# LocalizationBoard_B_1_0_Schematic_CG.net
KiCad netlist of a schematic drawn in Altium Designer
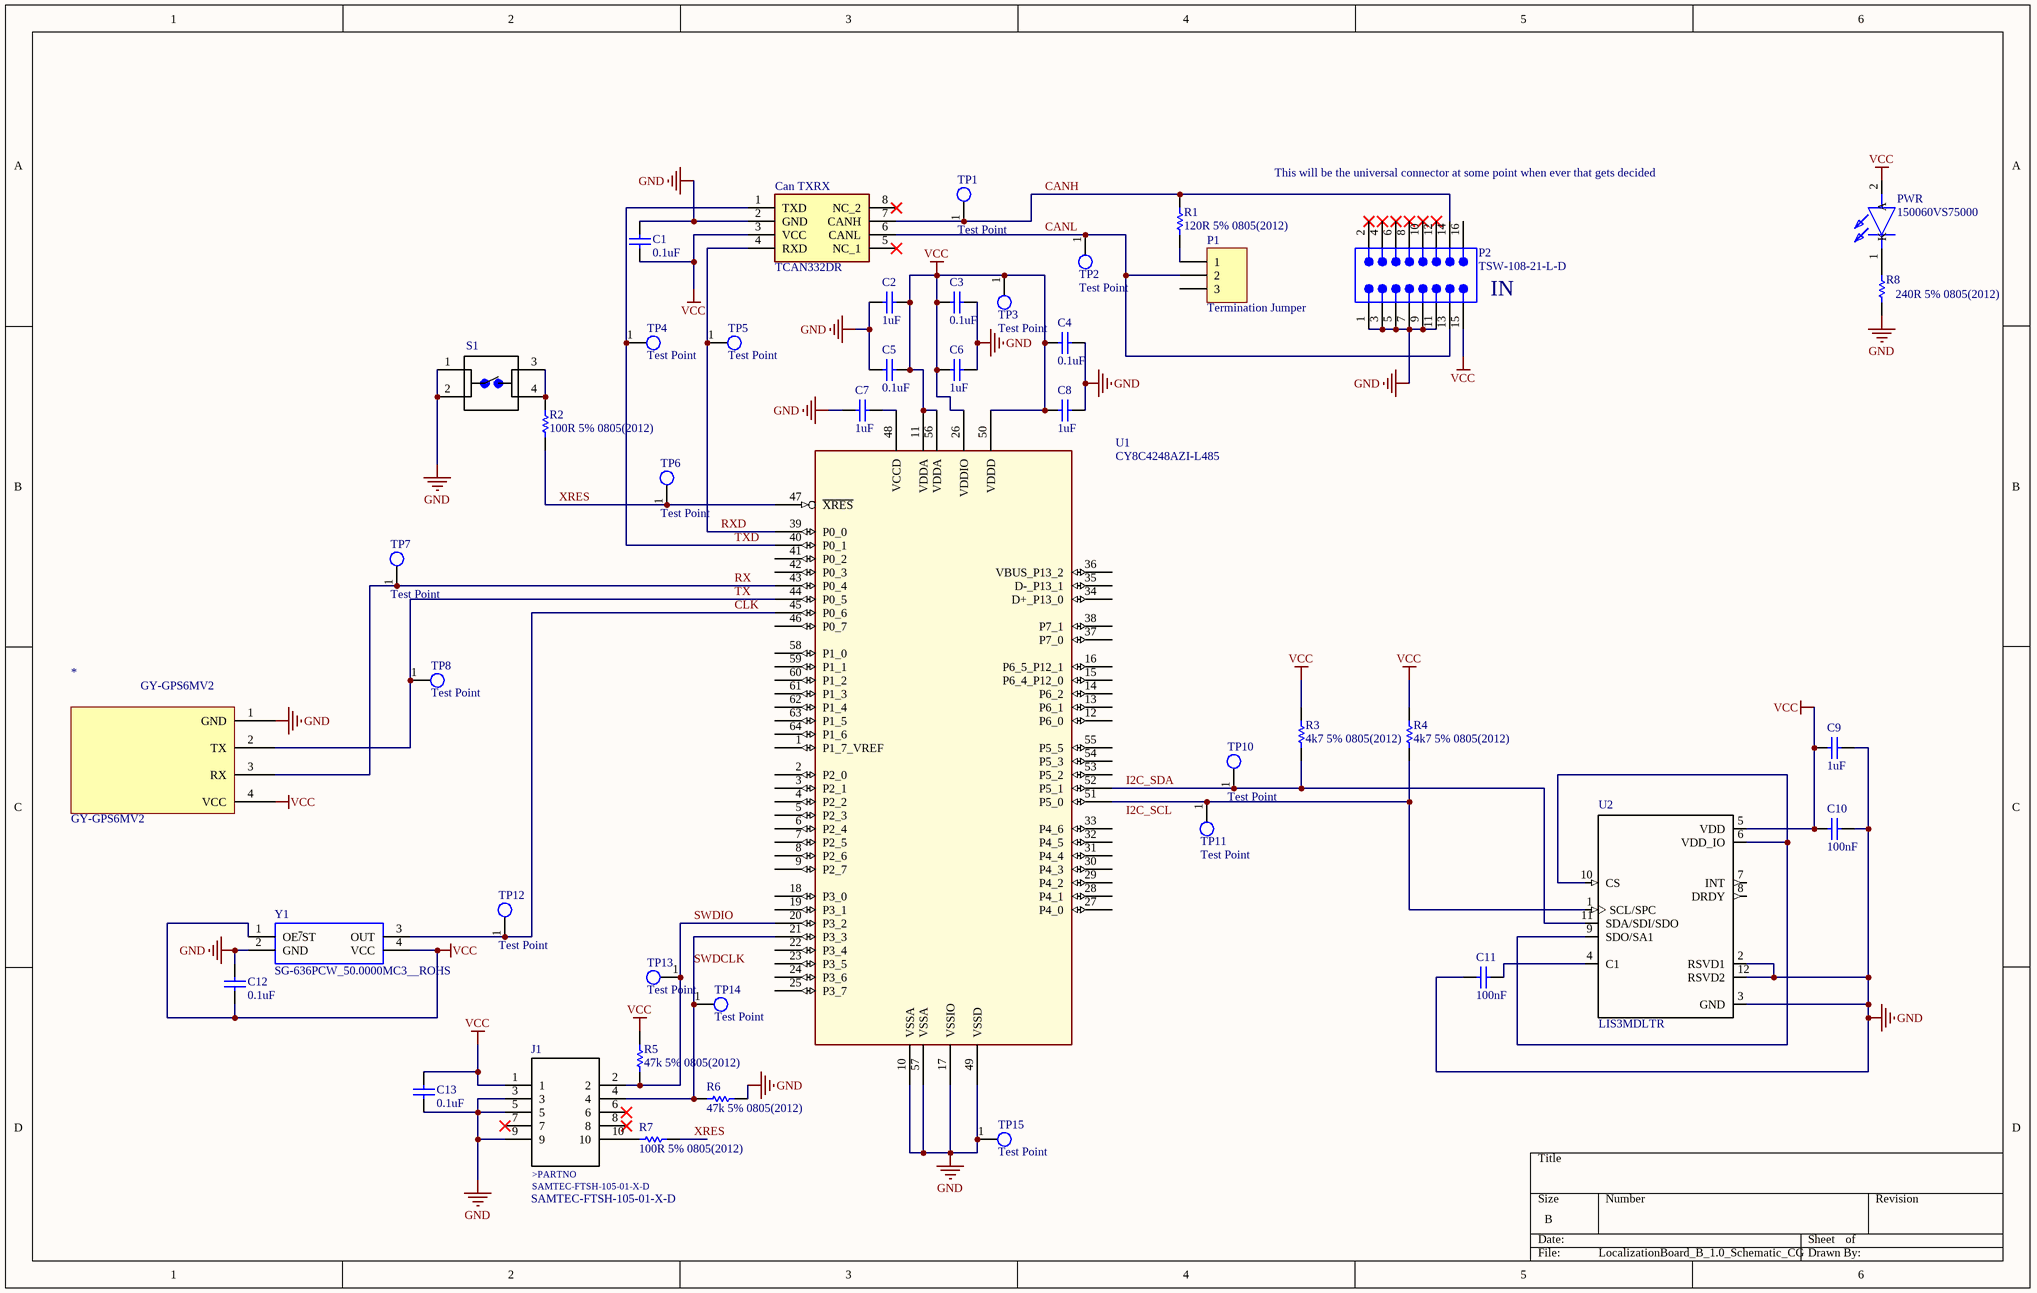
[diagram p0: LocalizationBoard_B_1.0_Schematic_CG.SchDoc]

(export (version "E")
  (design (tool "Eeschema 10.0.6"))
  (components
    (comp (ref "*")
      (value "GY-GPS6MV2")
      (footprint "PCBComponent_1 - duplicate2")
      (libsource (lib "Husky Robotics Standard Library 2019-2020") (part "GY-GPS6MV2"))
    )
    (comp (ref "C1")
      (value "0.1uF")
      (footprint "CAPC0805(2012)100_M")
      (description "CAP 33pF 200V ±1% 0805 (2012 Metric) Thickness 1mm SMD")
      (fields (field (name "TOLERANCE") "Â±1%"))
      (libsource (lib "Altium Content Vault") (part "CAP"))
    )
    (comp (ref "C2")
      (value "1uF")
      (footprint "CAPC0805(2012)100_M")
      (description "CAP 33pF 200V ±1% 0805 (2012 Metric) Thickness 1mm SMD")
      (fields (field (name "TOLERANCE") "Â±1%"))
      (libsource (lib "Altium Content Vault") (part "CAP"))
    )
    (comp (ref "C3")
      (value "0.1uF")
      (footprint "CAPC0805(2012)100_M")
      (description "CAP 33pF 200V ±1% 0805 (2012 Metric) Thickness 1mm SMD")
      (fields (field (name "TOLERANCE") "Â±1%"))
      (libsource (lib "Altium Content Vault") (part "CAP"))
    )
    (comp (ref "C4")
      (value "0.1uF")
      (footprint "CAPC0805(2012)100_N")
      (description "CAP 33pF 200V ±1% 0805 (2012 Metric) Thickness 1mm SMD")
      (fields (field (name "TOLERANCE") "Â±1%"))
      (libsource (lib "Altium Content Vault") (part "CAP"))
    )
    (comp (ref "C5")
      (value "0.1uF")
      (footprint "CAPC0805(2012)100_M")
      (description "CAP 33pF 200V ±1% 0805 (2012 Metric) Thickness 1mm SMD")
      (fields (field (name "TOLERANCE") "Â±1%"))
      (libsource (lib "Altium Content Vault") (part "CAP"))
    )
    (comp (ref "C6")
      (value "1uF")
      (footprint "CAPC0805(2012)100_M")
      (description "CAP 33pF 200V ±1% 0805 (2012 Metric) Thickness 1mm SMD")
      (fields (field (name "TOLERANCE") "Â±1%"))
      (libsource (lib "Altium Content Vault") (part "CAP"))
    )
    (comp (ref "C7")
      (value "1uF")
      (footprint "CAPC0805(2012)100_M")
      (description "CAP 33pF 200V ±1% 0805 (2012 Metric) Thickness 1mm SMD")
      (fields (field (name "TOLERANCE") "Â±1%"))
      (libsource (lib "Altium Content Vault") (part "CAP"))
    )
    (comp (ref "C8")
      (value "1uF")
      (footprint "CAPC0805(2012)100_M")
      (description "CAP 33pF 200V ±1% 0805 (2012 Metric) Thickness 1mm SMD")
      (fields (field (name "TOLERANCE") "Â±1%"))
      (libsource (lib "Altium Content Vault") (part "CAP"))
    )
    (comp (ref "C9")
      (value "1uF")
      (footprint "CAPC0805(2012)100_M")
      (description "CAP 33pF 200V ±1% 0805 (2012 Metric) Thickness 1mm SMD")
      (fields (field (name "TOLERANCE") "Â±1%"))
      (libsource (lib "Altium Content Vault") (part "CAP"))
    )
    (comp (ref "C10")
      (value "100nF")
      (footprint "CAPC0805(2012)100_M")
      (description "CAP 33pF 200V ±1% 0805 (2012 Metric) Thickness 1mm SMD")
      (fields (field (name "TOLERANCE") "Â±1%"))
      (libsource (lib "Altium Content Vault") (part "CAP"))
    )
    (comp (ref "C11")
      (value "100nF")
      (footprint "CAPC0805(2012)100_M")
      (description "CAP 33pF 200V ±1% 0805 (2012 Metric) Thickness 1mm SMD")
      (fields (field (name "TOLERANCE") "Â±1%"))
      (libsource (lib "Altium Content Vault") (part "CAP"))
    )
    (comp (ref "C12")
      (value "0.1uF")
      (footprint "CAPC0805(2012)100_M")
      (description "CAP 33pF 200V ±1% 0805 (2012 Metric) Thickness 1mm SMD")
      (fields (field (name "TOLERANCE") "Â±1%"))
      (libsource (lib "Altium Content Vault") (part "CAP"))
    )
    (comp (ref "C13")
      (value "0.1uF")
      (footprint "CAPC0805(2012)100_M")
      (description "CAP 33pF 200V ±1% 0805 (2012 Metric) Thickness 1mm SMD")
      (fields (field (name "TOLERANCE") "Â±1%"))
      (libsource (lib "Altium Content Vault") (part "CAP"))
    )
    (comp (ref "Can TXRX")
      (value "TCAN332DR")
      (footprint "SamacSys:SOIC127P600X175-8N")
      (description "Integrated Circuit")
      (fields (field (name "MOUSER PART NUMBER") "595-TCAN332DR"))
      (libsource (lib "*") (part "TCAN332DR"))
    )
    (comp (ref "J1")
      (value "SAMTEC-FTSH-105-01-X-D")
      (footprint "SAMTEC-FTSH-105-01-X-D")
      (libsource (lib "Husky Robotics Standard Library 2019-2020") (part "SAMTEC-FTSH-105-01-X-D"))
    )
    (comp (ref "P1")
      (value "Termination Jumper")
      (footprint "HDR1X3")
      (description "Header, 3-Pin")
      (fields (field (name "PUBLISHER") "Altium Limited"))
      (libsource (lib "Miscellaneous Connectors") (part "Header 3"))
    )
    (comp (ref "P2")
      (value "TSW-108-21-L-D")
      (footprint "SMTC-TSW-108-21-X-D")
      (fields (field (name "MANUFACTURER") "Samtec"))
      (libsource (lib "Altium Content Vault") (part "SMTC-TSW-108-X-X-D"))
    )
    (comp (ref "PWR")
      (value "150060VS75000")
      (footprint "SamacSys:LEDC1608X80N")
      (description "LED")
      (fields
        (field (name "MOUSER PART NUMBER") "710-150060VS75000")
        (field (name "RS PART NUMBER") "8154215P")
      )
      (libsource (lib "*") (part "150060VS75000"))
    )
    (comp (ref "R1")
      (value "120R 5% 0805(2012)")
      (footprint "RESC0805(2012)_N")
      (description "120R 0.125W 5% 0805 (2012 Metric)  SMD")
      (fields (field (name "TOLERANCE") "5 %") (field (name "POWER") "0.125 W"))
      (libsource (lib "Husky Robotics Standard Library 2019-2020") (part "120R 5% 0805"))
    )
    (comp (ref "R2")
      (value "100R 5% 0805(2012)")
      (footprint "RESC0805(2012)_N")
      (description "120R 0.125W 5% 0805 (2012 Metric)  SMD")
      (fields (field (name "TOLERANCE") "5 %") (field (name "POWER") "0.125 W"))
      (libsource (lib "Husky Robotics Standard Library 2019-2020") (part "120R 5% 0805"))
    )
    (comp (ref "R3")
      (value "4k7 5% 0805(2012)")
      (footprint "RESC0805(2012)_N")
      (description "120R 0.125W 5% 0805 (2012 Metric)  SMD")
      (fields (field (name "TOLERANCE") "5 %") (field (name "POWER") "0.125 W"))
      (libsource (lib "Husky Robotics Standard Library 2019-2020") (part "120R 5% 0805"))
    )
    (comp (ref "R4")
      (value "4k7 5% 0805(2012)")
      (footprint "RESC0805(2012)_N")
      (description "120R 0.125W 5% 0805 (2012 Metric)  SMD")
      (fields (field (name "TOLERANCE") "5 %") (field (name "POWER") "0.125 W"))
      (libsource (lib "Husky Robotics Standard Library 2019-2020") (part "120R 5% 0805"))
    )
    (comp (ref "R5")
      (value "47k 5% 0805(2012)")
      (footprint "RESC0805(2012)_N")
      (description "120R 0.125W 5% 0805 (2012 Metric)  SMD")
      (fields (field (name "TOLERANCE") "5 %") (field (name "POWER") "0.125 W"))
      (libsource (lib "Husky Robotics Standard Library 2019-2020") (part "120R 5% 0805"))
    )
    (comp (ref "R6")
      (value "47k 5% 0805(2012)")
      (footprint "RESC0805(2012)_N")
      (description "120R 0.125W 5% 0805 (2012 Metric)  SMD")
      (fields (field (name "TOLERANCE") "5 %") (field (name "POWER") "0.125 W"))
      (libsource (lib "Husky Robotics Standard Library 2019-2020") (part "120R 5% 0805"))
    )
    (comp (ref "R7")
      (value "100R 5% 0805(2012)")
      (footprint "RESC0805(2012)_N")
      (description "120R 0.125W 5% 0805 (2012 Metric)  SMD")
      (fields (field (name "TOLERANCE") "5 %") (field (name "POWER") "0.125 W"))
      (libsource (lib "Husky Robotics Standard Library 2019-2020") (part "120R 5% 0805"))
    )
    (comp (ref "R8")
      (value "240R 5% 0805(2012)")
      (footprint "RESC0805(2012)_N")
      (description "120R 0.125W 5% 0805 (2012 Metric)  SMD")
      (fields (field (name "TOLERANCE") "5 %") (field (name "POWER") "0.125 W"))
      (libsource (lib "Husky Robotics Standard Library 2019-2020") (part "120R 5% 0805"))
    )
    (comp (ref "S1")
      (value "1825910-7")
      (footprint "Switch 6mm 24V (NO)")
      (description "FSM4JAH=6MM TACT SWITCH, HIGH TEMP")
      (fields (field (name "MF") "TE Connectivity") (field (name "DIGI-KEY_PART_NUMBER") "450-1804-ND"))
      (libsource (lib "Husky Robotics Standard Library 2019-2020") (part "Switch 6mm 24V (NO)"))
    )
    (comp (ref "TP1")
      (value "Test Point")
      (footprint "Test Point Through-hole")
      (libsource (lib "Husky Robotics Standard Library 2019-2020") (part "Test Point"))
    )
    (comp (ref "TP2")
      (value "Test Point")
      (footprint "Test Point Through-hole")
      (libsource (lib "Husky Robotics Standard Library 2019-2020") (part "Test Point"))
    )
    (comp (ref "TP3")
      (value "Test Point")
      (footprint "Test Point Through-hole")
      (libsource (lib "Husky Robotics Standard Library 2019-2020") (part "Test Point"))
    )
    (comp (ref "TP4")
      (value "Test Point")
      (footprint "Test Point Through-hole")
      (libsource (lib "Husky Robotics Standard Library 2019-2020") (part "Test Point"))
    )
    (comp (ref "TP5")
      (value "Test Point")
      (footprint "Test Point Through-hole")
      (libsource (lib "Husky Robotics Standard Library 2019-2020") (part "Test Point"))
    )
    (comp (ref "TP6")
      (value "Test Point")
      (footprint "Test Point Through-hole")
      (libsource (lib "Husky Robotics Standard Library 2019-2020") (part "Test Point"))
    )
    (comp (ref "TP7")
      (value "Test Point")
      (footprint "Test Point Through-hole")
      (libsource (lib "Husky Robotics Standard Library 2019-2020") (part "Test Point"))
    )
    (comp (ref "TP8")
      (value "Test Point")
      (footprint "Test Point Through-hole")
      (libsource (lib "Husky Robotics Standard Library 2019-2020") (part "Test Point"))
    )
    (comp (ref "TP10")
      (value "Test Point")
      (footprint "Test Point Through-hole")
      (libsource (lib "Husky Robotics Standard Library 2019-2020") (part "Test Point"))
    )
    (comp (ref "TP11")
      (value "Test Point")
      (footprint "Test Point Through-hole")
      (libsource (lib "Husky Robotics Standard Library 2019-2020") (part "Test Point"))
    )
    (comp (ref "TP12")
      (value "Test Point")
      (footprint "Test Point Through-hole")
      (libsource (lib "Husky Robotics Standard Library 2019-2020") (part "Test Point"))
    )
    (comp (ref "TP13")
      (value "Test Point")
      (footprint "Test Point Through-hole")
      (libsource (lib "Husky Robotics Standard Library 2019-2020") (part "Test Point"))
    )
    (comp (ref "TP14")
      (value "Test Point")
      (footprint "Test Point Through-hole")
      (libsource (lib "Husky Robotics Standard Library 2019-2020") (part "Test Point"))
    )
    (comp (ref "TP15")
      (value "Test Point")
      (footprint "Test Point Through-hole")
      (libsource (lib "Husky Robotics Standard Library 2019-2020") (part "Test Point"))
    )
    (comp (ref "U1")
      (value "CY8C4248AZI-L485")
      (footprint "TQFP50P1200X1200X160-64N")
      (libsource (lib "Husky Robotics Standard Library 2019-2020") (part "CY8C4248AZI-L485"))
    )
    (comp (ref "U2")
      (value "LIS3MDLTR")
      (footprint "*XDCR_LIS3MDLTR")
      (description "LIS3MDL Series 3 Axis Â±2/Â±8/Â±12/Â±16 g 3.6V High Performance Magnetometer LGA-12")
      (fields (field (name "DIGI-KEY_PART_NUMBER") "497-13892-1-ND") (field (name "MF") "STMicroelectronics"))
      (libsource (lib "LIS3MDLTR") (part "LIS3MDLTR"))
    )
    (comp (ref "Y1")
      (value "SG-636PCW_50.0000MC3__ROHS")
      (footprint "SG-636")
      (description "Standard Clock Oscillators 50MHz 3.3Volt 100ppm -20C +70C")
      (fields (field (name "MANUFACTURER_PART_NUMBER") "SG-636PCW 50.0000MC3: ROHS"))
      (libsource (lib "Husky Robotics Standard Library 2019-2020") (part "SG-636"))
    )
  )
  (nets
    (net (code "1") (name "/CANH") (class "Default")
      (node (ref "Can TXRX") (pin "7") (pinfunction "CANH_7") (pintype "passive"))
      (node (ref "P2") (pin "14") (pinfunction "14_14") (pintype "passive"))
      (node (ref "R1") (pin "2") (pinfunction "2_2") (pintype "passive"))
      (node (ref "TP1") (pin "1") (pinfunction "1_1") (pintype "passive"))
    )
    (net (code "2") (name "/CANL") (class "Default")
      (node (ref "Can TXRX") (pin "6") (pinfunction "CANL_6") (pintype "passive"))
      (node (ref "P1") (pin "2") (pinfunction "2_2") (pintype "passive"))
      (node (ref "P2") (pin "13") (pinfunction "13_13") (pintype "passive"))
      (node (ref "TP2") (pin "1") (pinfunction "1_1") (pintype "passive"))
    )
    (net (code "3") (name "/CLK") (class "Default")
      (node (ref "TP12") (pin "1") (pinfunction "1_1") (pintype "passive"))
      (node (ref "U1") (pin "45") (pinfunction "P0_6_45") (pintype "bidirectional"))
      (node (ref "Y1") (pin "3") (pinfunction "OUT_3") (pintype "passive"))
    )
    (net (code "4") (name "/I2C_SCL") (class "Default")
      (node (ref "R4") (pin "1") (pinfunction "1_1") (pintype "passive"))
      (node (ref "TP11") (pin "1") (pinfunction "1_1") (pintype "passive"))
      (node (ref "U1") (pin "51") (pinfunction "P5_0_51") (pintype "bidirectional"))
      (node (ref "U2") (pin "1") (pinfunction "SCL/SPC_1") (pintype "input"))
    )
    (net (code "5") (name "/I2C_SDA") (class "Default")
      (node (ref "R3") (pin "1") (pinfunction "1_1") (pintype "passive"))
      (node (ref "TP10") (pin "1") (pinfunction "1_1") (pintype "passive"))
      (node (ref "U1") (pin "52") (pinfunction "P5_1_52") (pintype "bidirectional"))
      (node (ref "U2") (pin "11") (pinfunction "SDA/SDI/SDO_11") (pintype "bidirectional"))
    )
    (net (code "6") (name "/RX") (class "Default")
      (node (ref "*") (pin "3") (pinfunction "RX_3") (pintype "passive"))
      (node (ref "TP7") (pin "1") (pinfunction "1_1") (pintype "passive"))
      (node (ref "U1") (pin "43") (pinfunction "P0_4_43") (pintype "bidirectional"))
    )
    (net (code "7") (name "/RXD") (class "Default")
      (node (ref "Can TXRX") (pin "4") (pinfunction "RXD_4") (pintype "passive"))
      (node (ref "TP5") (pin "1") (pinfunction "1_1") (pintype "passive"))
      (node (ref "U1") (pin "39") (pinfunction "P0_0_39") (pintype "bidirectional"))
    )
    (net (code "8") (name "/SWDCLK") (class "Default")
      (node (ref "J1") (pin "4") (pinfunction "4_4") (pintype "passive"))
      (node (ref "R6") (pin "1") (pinfunction "1_1") (pintype "passive"))
      (node (ref "TP14") (pin "1") (pinfunction "1_1") (pintype "passive"))
      (node (ref "U1") (pin "21") (pinfunction "P3_3_21") (pintype "bidirectional"))
    )
    (net (code "9") (name "/SWDIO") (class "Default")
      (node (ref "J1") (pin "2") (pinfunction "2_2") (pintype "passive"))
      (node (ref "R5") (pin "1") (pinfunction "1_1") (pintype "passive"))
      (node (ref "TP13") (pin "1") (pinfunction "1_1") (pintype "passive"))
      (node (ref "U1") (pin "20") (pinfunction "P3_2_20") (pintype "bidirectional"))
    )
    (net (code "10") (name "/TX") (class "Default")
      (node (ref "*") (pin "2") (pinfunction "TX_2") (pintype "passive"))
      (node (ref "TP8") (pin "1") (pinfunction "1_1") (pintype "passive"))
      (node (ref "U1") (pin "44") (pinfunction "P0_5_44") (pintype "bidirectional"))
    )
    (net (code "11") (name "/TXD") (class "Default")
      (node (ref "Can TXRX") (pin "1") (pinfunction "TXD_1") (pintype "passive"))
      (node (ref "TP4") (pin "1") (pinfunction "1_1") (pintype "passive"))
      (node (ref "U1") (pin "40") (pinfunction "P0_1_40") (pintype "bidirectional"))
    )
    (net (code "12") (name "/XRES") (class "Default")
      (node (ref "R2") (pin "1") (pinfunction "1_1") (pintype "passive"))
      (node (ref "R7") (pin "1") (pinfunction "1_1") (pintype "passive"))
      (node (ref "TP6") (pin "1") (pinfunction "1_1") (pintype "passive"))
      (node (ref "U1") (pin "47") (pinfunction "~{XRES}_47") (pintype "input"))
    )
    (net (code "13") (name "GND") (class "Default")
      (node (ref "*") (pin "1") (pinfunction "GND_1") (pintype "passive"))
      (node (ref "C1") (pin "1") (pinfunction "1_1") (pintype "passive"))
      (node (ref "C10") (pin "1") (pinfunction "1_1") (pintype "passive"))
      (node (ref "C11") (pin "2") (pinfunction "2_2") (pintype "passive"))
      (node (ref "C12") (pin "1") (pinfunction "1_1") (pintype "passive"))
      (node (ref "C13") (pin "2") (pinfunction "2_2") (pintype "passive"))
      (node (ref "C2") (pin "2") (pinfunction "2_2") (pintype "passive"))
      (node (ref "C3") (pin "1") (pinfunction "1_1") (pintype "passive"))
      (node (ref "C4") (pin "1") (pinfunction "1_1") (pintype "passive"))
      (node (ref "C5") (pin "2") (pinfunction "2_2") (pintype "passive"))
      (node (ref "C6") (pin "1") (pinfunction "1_1") (pintype "passive"))
      (node (ref "C7") (pin "2") (pinfunction "2_2") (pintype "passive"))
      (node (ref "C8") (pin "1") (pinfunction "1_1") (pintype "passive"))
      (node (ref "C9") (pin "1") (pinfunction "1_1") (pintype "passive"))
      (node (ref "Can TXRX") (pin "2") (pinfunction "GND_2") (pintype "passive"))
      (node (ref "J1") (pin "3") (pinfunction "3_3") (pintype "passive"))
      (node (ref "J1") (pin "5") (pinfunction "5_5") (pintype "passive"))
      (node (ref "J1") (pin "9") (pinfunction "9_9") (pintype "passive"))
      (node (ref "P2") (pin "1") (pinfunction "1_1") (pintype "passive"))
      (node (ref "P2") (pin "11") (pinfunction "11_11") (pintype "passive"))
      (node (ref "P2") (pin "3") (pinfunction "3_3") (pintype "passive"))
      (node (ref "P2") (pin "5") (pinfunction "5_5") (pintype "passive"))
      (node (ref "P2") (pin "7") (pinfunction "7_7") (pintype "passive"))
      (node (ref "P2") (pin "9") (pinfunction "9_9") (pintype "passive"))
      (node (ref "R6") (pin "2") (pinfunction "2_2") (pintype "passive"))
      (node (ref "R8") (pin "1") (pinfunction "1_1") (pintype "passive"))
      (node (ref "S1") (pin "1") (pinfunction "1_1") (pintype "passive"))
      (node (ref "S1") (pin "2") (pinfunction "2_2") (pintype "passive"))
      (node (ref "TP15") (pin "1") (pinfunction "1_1") (pintype "passive"))
      (node (ref "U1") (pin "10") (pinfunction "VSSA_10") (pintype "power_in"))
      (node (ref "U1") (pin "17") (pinfunction "VSSIO_17") (pintype "power_in"))
      (node (ref "U1") (pin "49") (pinfunction "VSSD_49") (pintype "power_in"))
      (node (ref "U1") (pin "57") (pinfunction "VSSA_57") (pintype "power_in"))
      (node (ref "U2") (pin "12") (pinfunction "RSVD2_12") (pintype "passive"))
      (node (ref "U2") (pin "2") (pinfunction "RSVD1_2") (pintype "passive"))
      (node (ref "U2") (pin "3") (pinfunction "GND_3") (pintype "power_in"))
      (node (ref "Y1") (pin "2") (pinfunction "GND_2") (pintype "passive"))
    )
    (net (code "14") (name "Net-(J1-Pad10)") (class "Default")
      (node (ref "J1") (pin "10") (pinfunction "10_10") (pintype "passive"))
      (node (ref "R7") (pin "2") (pinfunction "2_2") (pintype "passive"))
    )
    (net (code "15") (name "Net-(P1-Pad1)") (class "Default")
      (node (ref "P1") (pin "1") (pinfunction "1_1") (pintype "passive"))
      (node (ref "R1") (pin "1") (pinfunction "1_1") (pintype "passive"))
    )
    (net (code "16") (name "Net-(PWR-K)") (class "Default")
      (node (ref "PWR") (pin "1") (pinfunction "K_1") (pintype "passive"))
      (node (ref "R8") (pin "2") (pinfunction "2_2") (pintype "passive"))
    )
    (net (code "17") (name "Net-(R2-Pad2)") (class "Default")
      (node (ref "R2") (pin "2") (pinfunction "2_2") (pintype "passive"))
      (node (ref "S1") (pin "3") (pinfunction "3_3") (pintype "passive"))
      (node (ref "S1") (pin "4") (pinfunction "4_4") (pintype "passive"))
    )
    (net (code "18") (name "Net-(U1-VCCD)") (class "Default")
      (node (ref "C7") (pin "1") (pinfunction "1_1") (pintype "passive"))
      (node (ref "U1") (pin "48") (pinfunction "VCCD_48") (pintype "power_in"))
    )
    (net (code "19") (name "Net-(U2-C1)") (class "Default")
      (node (ref "C11") (pin "1") (pinfunction "1_1") (pintype "passive"))
      (node (ref "U2") (pin "4") (pinfunction "C1_4") (pintype "passive"))
    )
    (net (code "20") (name "Net-(U2-CS)") (class "Default")
      (node (ref "U2") (pin "10") (pinfunction "CS_10") (pintype "input"))
      (node (ref "U2") (pin "6") (pinfunction "VDD_IO_6") (pintype "power_in"))
      (node (ref "U2") (pin "9") (pinfunction "SDO/SA1_9") (pintype "bidirectional"))
    )
    (net (code "21") (name "VCC") (class "Default")
      (node (ref "*") (pin "4") (pinfunction "VCC_4") (pintype "passive"))
      (node (ref "C1") (pin "2") (pinfunction "2_2") (pintype "passive"))
      (node (ref "C10") (pin "2") (pinfunction "2_2") (pintype "passive"))
      (node (ref "C12") (pin "2") (pinfunction "2_2") (pintype "passive"))
      (node (ref "C13") (pin "1") (pinfunction "1_1") (pintype "passive"))
      (node (ref "C2") (pin "1") (pinfunction "1_1") (pintype "passive"))
      (node (ref "C3") (pin "2") (pinfunction "2_2") (pintype "passive"))
      (node (ref "C4") (pin "2") (pinfunction "2_2") (pintype "passive"))
      (node (ref "C5") (pin "1") (pinfunction "1_1") (pintype "passive"))
      (node (ref "C6") (pin "2") (pinfunction "2_2") (pintype "passive"))
      (node (ref "C8") (pin "2") (pinfunction "2_2") (pintype "passive"))
      (node (ref "C9") (pin "2") (pinfunction "2_2") (pintype "passive"))
      (node (ref "Can TXRX") (pin "3") (pinfunction "VCC_3") (pintype "passive"))
      (node (ref "J1") (pin "1") (pinfunction "1_1") (pintype "passive"))
      (node (ref "P2") (pin "15") (pinfunction "15_15") (pintype "passive"))
      (node (ref "PWR") (pin "2") (pinfunction "A_2") (pintype "passive"))
      (node (ref "R3") (pin "2") (pinfunction "2_2") (pintype "passive"))
      (node (ref "R4") (pin "2") (pinfunction "2_2") (pintype "passive"))
      (node (ref "R5") (pin "2") (pinfunction "2_2") (pintype "passive"))
      (node (ref "TP3") (pin "1") (pinfunction "1_1") (pintype "passive"))
      (node (ref "U1") (pin "11") (pinfunction "VDDA_11") (pintype "power_in"))
      (node (ref "U1") (pin "26") (pinfunction "VDDIO_26") (pintype "power_in"))
      (node (ref "U1") (pin "50") (pinfunction "VDDD_50") (pintype "power_in"))
      (node (ref "U1") (pin "56") (pinfunction "VDDA_56") (pintype "power_in"))
      (node (ref "U2") (pin "5") (pinfunction "VDD_5") (pintype "power_in"))
      (node (ref "Y1") (pin "1") (pinfunction "OE~{/}ST_1") (pintype "passive"))
      (node (ref "Y1") (pin "4") (pinfunction "VCC_4") (pintype "power_in"))
    )
    (net (code "22") (name "unconnected-(Can TXRX-NC_1-Pad5)") (class "Default")
      (node (ref "Can TXRX") (pin "5") (pinfunction "NC_1_5") (pintype "passive+no_connect"))
    )
    (net (code "23") (name "unconnected-(Can TXRX-NC_2-Pad8)") (class "Default")
      (node (ref "Can TXRX") (pin "8") (pinfunction "NC_2_8") (pintype "passive+no_connect"))
    )
    (net (code "24") (name "unconnected-(J1-Pad6)") (class "Default")
      (node (ref "J1") (pin "6") (pinfunction "6_6") (pintype "passive+no_connect"))
    )
    (net (code "25") (name "unconnected-(J1-Pad7)") (class "Default")
      (node (ref "J1") (pin "7") (pinfunction "7_7") (pintype "passive+no_connect"))
    )
    (net (code "26") (name "unconnected-(J1-Pad8)") (class "Default")
      (node (ref "J1") (pin "8") (pinfunction "8_8") (pintype "passive+no_connect"))
    )
    (net (code "27") (name "unconnected-(P1-Pad3)") (class "Default")
      (node (ref "P1") (pin "3") (pinfunction "3_3") (pintype "passive"))
    )
    (net (code "28") (name "unconnected-(P2-Pad2)") (class "Default")
      (node (ref "P2") (pin "2") (pinfunction "2_2") (pintype "passive+no_connect"))
    )
    (net (code "29") (name "unconnected-(P2-Pad4)") (class "Default")
      (node (ref "P2") (pin "4") (pinfunction "4_4") (pintype "passive+no_connect"))
    )
    (net (code "30") (name "unconnected-(P2-Pad6)") (class "Default")
      (node (ref "P2") (pin "6") (pinfunction "6_6") (pintype "passive+no_connect"))
    )
    (net (code "31") (name "unconnected-(P2-Pad8)") (class "Default")
      (node (ref "P2") (pin "8") (pinfunction "8_8") (pintype "passive+no_connect"))
    )
    (net (code "32") (name "unconnected-(P2-Pad10)") (class "Default")
      (node (ref "P2") (pin "10") (pinfunction "10_10") (pintype "passive+no_connect"))
    )
    (net (code "33") (name "unconnected-(P2-Pad12)") (class "Default")
      (node (ref "P2") (pin "12") (pinfunction "12_12") (pintype "passive+no_connect"))
    )
    (net (code "34") (name "unconnected-(P2-Pad16)") (class "Default")
      (node (ref "P2") (pin "16") (pinfunction "16_16") (pintype "passive"))
    )
    (net (code "35") (name "unconnected-(U1-D+_P13_0-Pad34)") (class "Default")
      (node (ref "U1") (pin "34") (pinfunction "D+_P13_0_34") (pintype "bidirectional"))
    )
    (net (code "36") (name "unconnected-(U1-D-_P13_1-Pad35)") (class "Default")
      (node (ref "U1") (pin "35") (pinfunction "D-_P13_1_35") (pintype "bidirectional"))
    )
    (net (code "37") (name "unconnected-(U1-P0_2-Pad41)") (class "Default")
      (node (ref "U1") (pin "41") (pinfunction "P0_2_41") (pintype "bidirectional"))
    )
    (net (code "38") (name "unconnected-(U1-P0_3-Pad42)") (class "Default")
      (node (ref "U1") (pin "42") (pinfunction "P0_3_42") (pintype "bidirectional"))
    )
    (net (code "39") (name "unconnected-(U1-P0_7-Pad46)") (class "Default")
      (node (ref "U1") (pin "46") (pinfunction "P0_7_46") (pintype "bidirectional"))
    )
    (net (code "40") (name "unconnected-(U1-P1_0-Pad58)") (class "Default")
      (node (ref "U1") (pin "58") (pinfunction "P1_0_58") (pintype "bidirectional"))
    )
    (net (code "41") (name "unconnected-(U1-P1_1-Pad59)") (class "Default")
      (node (ref "U1") (pin "59") (pinfunction "P1_1_59") (pintype "bidirectional"))
    )
    (net (code "42") (name "unconnected-(U1-P1_2-Pad60)") (class "Default")
      (node (ref "U1") (pin "60") (pinfunction "P1_2_60") (pintype "bidirectional"))
    )
    (net (code "43") (name "unconnected-(U1-P1_3-Pad61)") (class "Default")
      (node (ref "U1") (pin "61") (pinfunction "P1_3_61") (pintype "bidirectional"))
    )
    (net (code "44") (name "unconnected-(U1-P1_4-Pad62)") (class "Default")
      (node (ref "U1") (pin "62") (pinfunction "P1_4_62") (pintype "bidirectional"))
    )
    (net (code "45") (name "unconnected-(U1-P1_5-Pad63)") (class "Default")
      (node (ref "U1") (pin "63") (pinfunction "P1_5_63") (pintype "bidirectional"))
    )
    (net (code "46") (name "unconnected-(U1-P1_6-Pad64)") (class "Default")
      (node (ref "U1") (pin "64") (pinfunction "P1_6_64") (pintype "bidirectional"))
    )
    (net (code "47") (name "unconnected-(U1-P1_7_VREF-Pad1)") (class "Default")
      (node (ref "U1") (pin "1") (pinfunction "P1_7_VREF_1") (pintype "bidirectional"))
    )
    (net (code "48") (name "unconnected-(U1-P2_0-Pad2)") (class "Default")
      (node (ref "U1") (pin "2") (pinfunction "P2_0_2") (pintype "bidirectional"))
    )
    (net (code "49") (name "unconnected-(U1-P2_1-Pad3)") (class "Default")
      (node (ref "U1") (pin "3") (pinfunction "P2_1_3") (pintype "bidirectional"))
    )
    (net (code "50") (name "unconnected-(U1-P2_2-Pad4)") (class "Default")
      (node (ref "U1") (pin "4") (pinfunction "P2_2_4") (pintype "bidirectional"))
    )
    (net (code "51") (name "unconnected-(U1-P2_3-Pad5)") (class "Default")
      (node (ref "U1") (pin "5") (pinfunction "P2_3_5") (pintype "bidirectional"))
    )
    (net (code "52") (name "unconnected-(U1-P2_4-Pad6)") (class "Default")
      (node (ref "U1") (pin "6") (pinfunction "P2_4_6") (pintype "bidirectional"))
    )
    (net (code "53") (name "unconnected-(U1-P2_5-Pad7)") (class "Default")
      (node (ref "U1") (pin "7") (pinfunction "P2_5_7") (pintype "bidirectional"))
    )
    (net (code "54") (name "unconnected-(U1-P2_6-Pad8)") (class "Default")
      (node (ref "U1") (pin "8") (pinfunction "P2_6_8") (pintype "bidirectional"))
    )
    (net (code "55") (name "unconnected-(U1-P2_7-Pad9)") (class "Default")
      (node (ref "U1") (pin "9") (pinfunction "P2_7_9") (pintype "bidirectional"))
    )
    (net (code "56") (name "unconnected-(U1-P3_0-Pad18)") (class "Default")
      (node (ref "U1") (pin "18") (pinfunction "P3_0_18") (pintype "bidirectional"))
    )
    (net (code "57") (name "unconnected-(U1-P3_1-Pad19)") (class "Default")
      (node (ref "U1") (pin "19") (pinfunction "P3_1_19") (pintype "bidirectional"))
    )
    (net (code "58") (name "unconnected-(U1-P3_4-Pad22)") (class "Default")
      (node (ref "U1") (pin "22") (pinfunction "P3_4_22") (pintype "bidirectional"))
    )
    (net (code "59") (name "unconnected-(U1-P3_5-Pad23)") (class "Default")
      (node (ref "U1") (pin "23") (pinfunction "P3_5_23") (pintype "bidirectional"))
    )
    (net (code "60") (name "unconnected-(U1-P3_6-Pad24)") (class "Default")
      (node (ref "U1") (pin "24") (pinfunction "P3_6_24") (pintype "bidirectional"))
    )
    (net (code "61") (name "unconnected-(U1-P3_7-Pad25)") (class "Default")
      (node (ref "U1") (pin "25") (pinfunction "P3_7_25") (pintype "bidirectional"))
    )
    (net (code "62") (name "unconnected-(U1-P4_0-Pad27)") (class "Default")
      (node (ref "U1") (pin "27") (pinfunction "P4_0_27") (pintype "bidirectional"))
    )
    (net (code "63") (name "unconnected-(U1-P4_1-Pad28)") (class "Default")
      (node (ref "U1") (pin "28") (pinfunction "P4_1_28") (pintype "bidirectional"))
    )
    (net (code "64") (name "unconnected-(U1-P4_2-Pad29)") (class "Default")
      (node (ref "U1") (pin "29") (pinfunction "P4_2_29") (pintype "bidirectional"))
    )
    (net (code "65") (name "unconnected-(U1-P4_3-Pad30)") (class "Default")
      (node (ref "U1") (pin "30") (pinfunction "P4_3_30") (pintype "bidirectional"))
    )
    (net (code "66") (name "unconnected-(U1-P4_4-Pad31)") (class "Default")
      (node (ref "U1") (pin "31") (pinfunction "P4_4_31") (pintype "bidirectional"))
    )
    (net (code "67") (name "unconnected-(U1-P4_5-Pad32)") (class "Default")
      (node (ref "U1") (pin "32") (pinfunction "P4_5_32") (pintype "bidirectional"))
    )
    (net (code "68") (name "unconnected-(U1-P4_6-Pad33)") (class "Default")
      (node (ref "U1") (pin "33") (pinfunction "P4_6_33") (pintype "bidirectional"))
    )
    (net (code "69") (name "unconnected-(U1-P5_2-Pad53)") (class "Default")
      (node (ref "U1") (pin "53") (pinfunction "P5_2_53") (pintype "bidirectional"))
    )
    (net (code "70") (name "unconnected-(U1-P5_3-Pad54)") (class "Default")
      (node (ref "U1") (pin "54") (pinfunction "P5_3_54") (pintype "bidirectional"))
    )
    (net (code "71") (name "unconnected-(U1-P5_5-Pad55)") (class "Default")
      (node (ref "U1") (pin "55") (pinfunction "P5_5_55") (pintype "bidirectional"))
    )
    (net (code "72") (name "unconnected-(U1-P6_0-Pad12)") (class "Default")
      (node (ref "U1") (pin "12") (pinfunction "P6_0_12") (pintype "bidirectional"))
    )
    (net (code "73") (name "unconnected-(U1-P6_1-Pad13)") (class "Default")
      (node (ref "U1") (pin "13") (pinfunction "P6_1_13") (pintype "bidirectional"))
    )
    (net (code "74") (name "unconnected-(U1-P6_2-Pad14)") (class "Default")
      (node (ref "U1") (pin "14") (pinfunction "P6_2_14") (pintype "bidirectional"))
    )
    (net (code "75") (name "unconnected-(U1-P6_4_P12_0-Pad15)") (class "Default")
      (node (ref "U1") (pin "15") (pinfunction "P6_4_P12_0_15") (pintype "bidirectional"))
    )
    (net (code "76") (name "unconnected-(U1-P6_5_P12_1-Pad16)") (class "Default")
      (node (ref "U1") (pin "16") (pinfunction "P6_5_P12_1_16") (pintype "bidirectional"))
    )
    (net (code "77") (name "unconnected-(U1-P7_0-Pad37)") (class "Default")
      (node (ref "U1") (pin "37") (pinfunction "P7_0_37") (pintype "bidirectional"))
    )
    (net (code "78") (name "unconnected-(U1-P7_1-Pad38)") (class "Default")
      (node (ref "U1") (pin "38") (pinfunction "P7_1_38") (pintype "bidirectional"))
    )
    (net (code "79") (name "unconnected-(U1-VBUS_P13_2-Pad36)") (class "Default")
      (node (ref "U1") (pin "36") (pinfunction "VBUS_P13_2_36") (pintype "bidirectional"))
    )
    (net (code "80") (name "unconnected-(U2-DRDY-Pad8)") (class "Default")
      (node (ref "U2") (pin "8") (pinfunction "DRDY_8") (pintype "output"))
    )
    (net (code "81") (name "unconnected-(U2-INT-Pad7)") (class "Default")
      (node (ref "U2") (pin "7") (pinfunction "INT_7") (pintype "output"))
    )
  )
)
